# TRL-calibration-thru-reflect-match.net
KiCad netlist of a schematic drawn in EAGLE
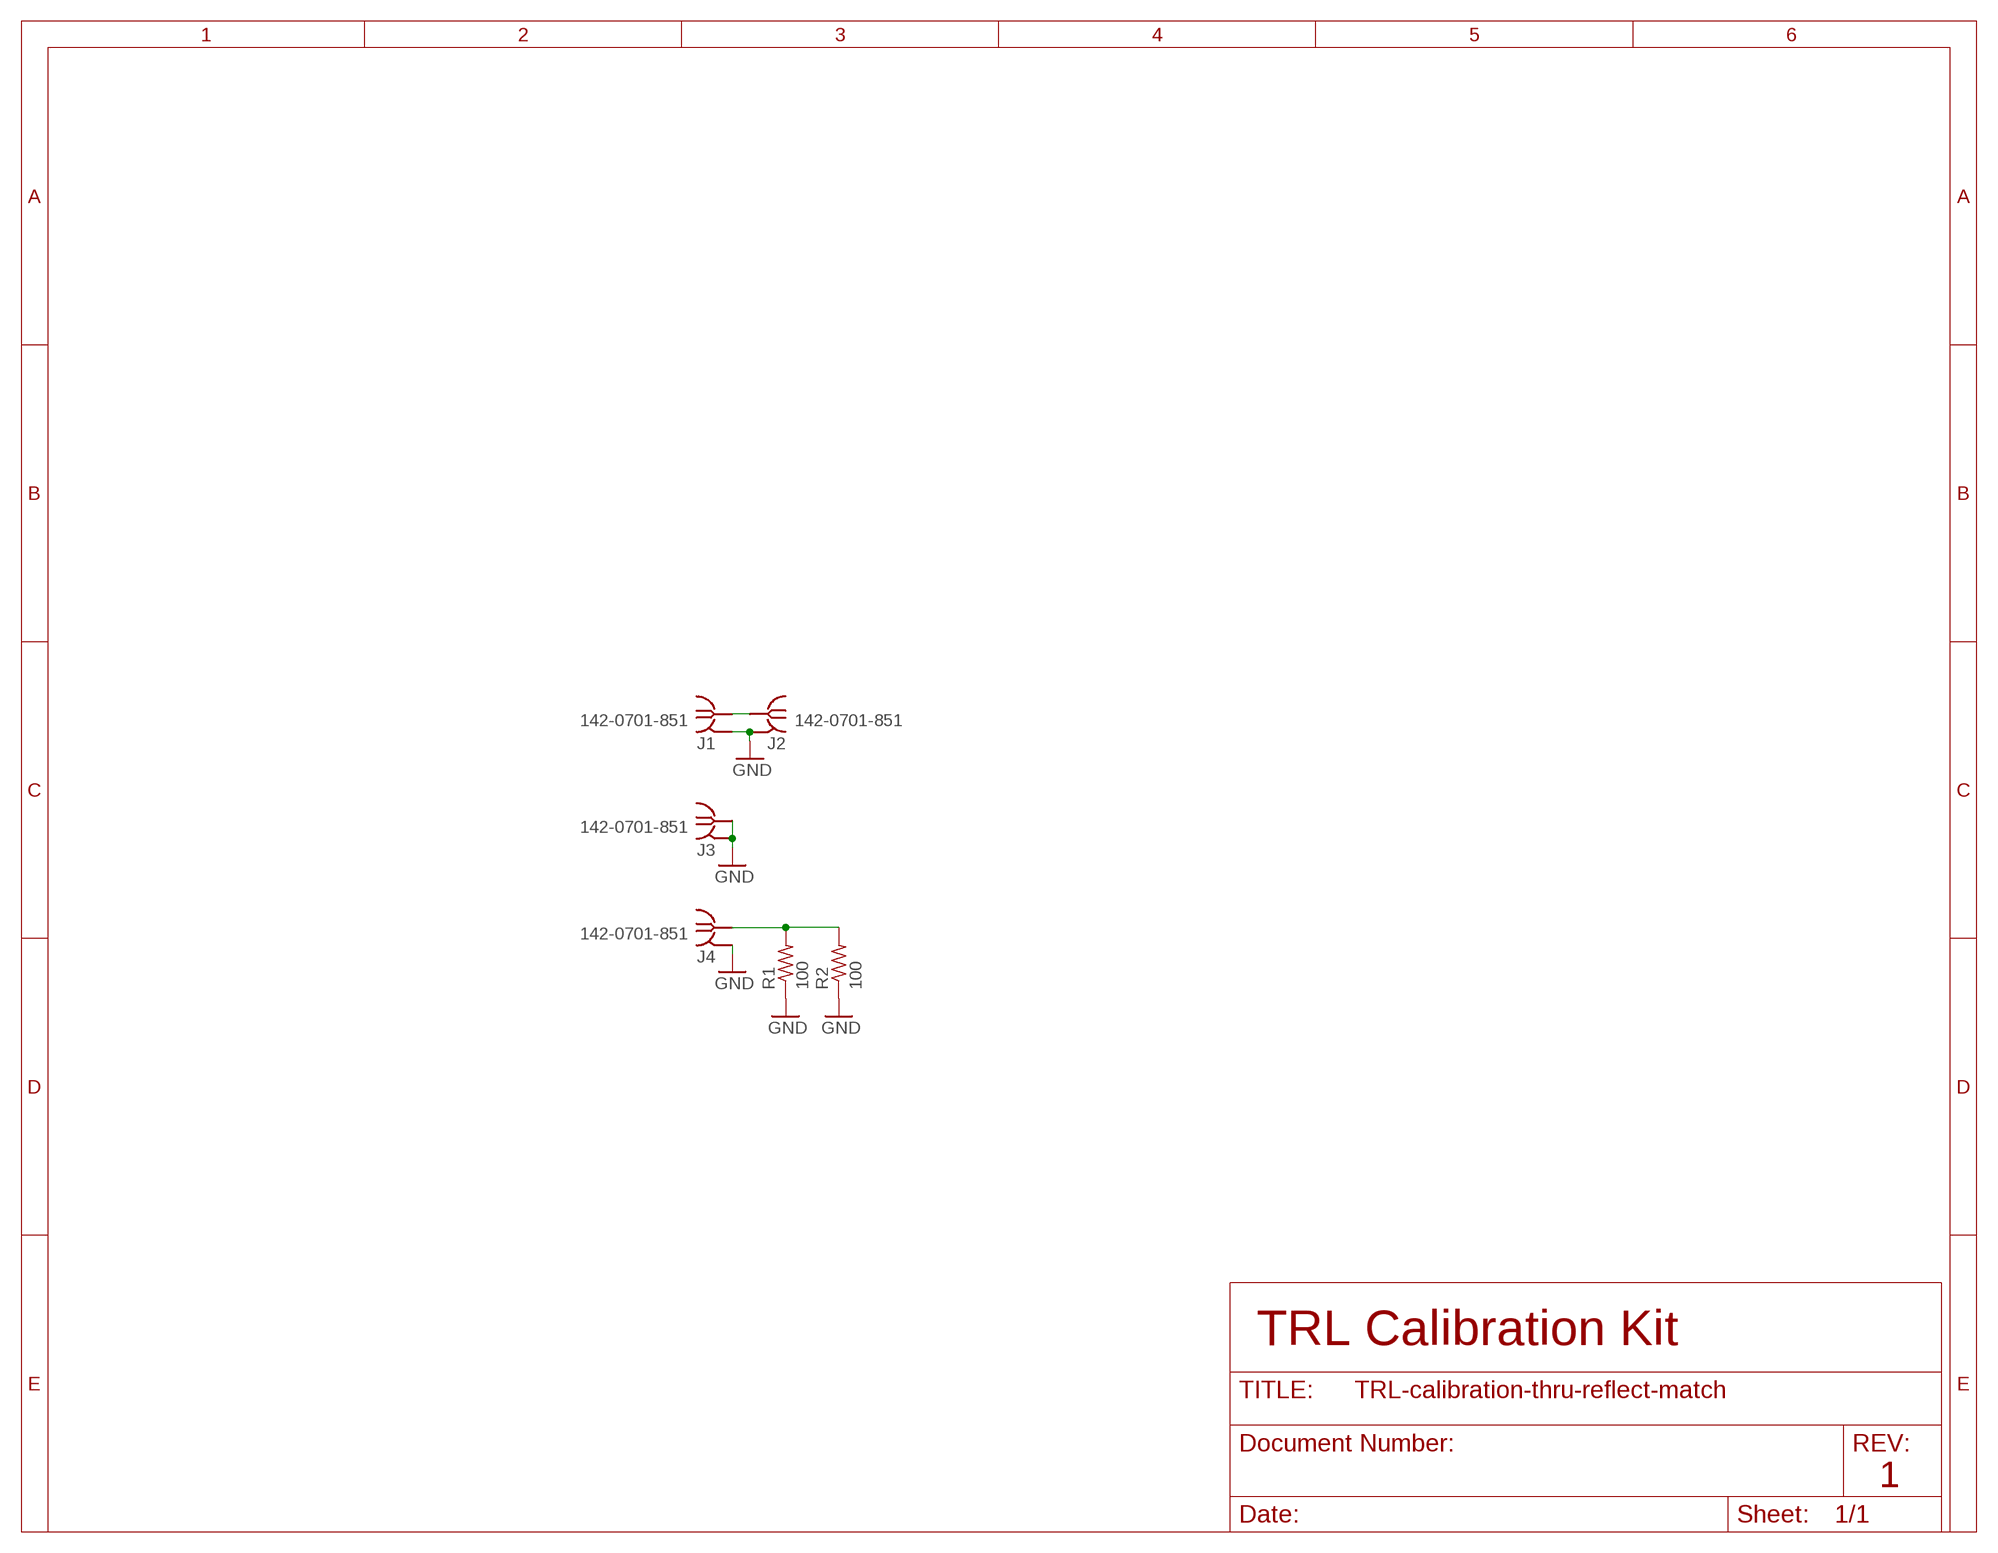
[diagram p0: schematic, sheet 1]

(export (version "E")
  (design (tool "Eeschema 10.0.6"))
  (components
    (comp (ref "J1")
      (value "142-0701-851")
      (footprint "eagle-import:142-0701-851")
      (libsource (lib "eagle-import") (part "142-0701-851"))
    )
    (comp (ref "J2")
      (value "142-0701-851")
      (footprint "eagle-import:142-0701-851")
      (libsource (lib "eagle-import") (part "142-0701-851"))
    )
    (comp (ref "J3")
      (value "142-0701-851")
      (footprint "eagle-import:142-0701-851")
      (libsource (lib "eagle-import") (part "142-0701-851"))
    )
    (comp (ref "J4")
      (value "142-0701-851")
      (footprint "eagle-import:142-0701-851")
      (libsource (lib "eagle-import") (part "142-0701-851"))
    )
    (comp (ref "R1")
      (value "100")
      (footprint "eagle-import:.0402-C-NOSILK")
      (libsource (lib "eagle-import") (part "R-US_0402-C-NOSILK"))
    )
    (comp (ref "R2")
      (value "100")
      (footprint "eagle-import:.0402-C-NOSILK")
      (libsource (lib "eagle-import") (part "R-US_0402-C-NOSILK"))
    )
  )
  (nets
    (net (code "1") (name "GND") (class "Default")
      (node (ref "J1") (pin "GND1") (pinfunction "GND_GND1") (pintype "bidirectional"))
      (node (ref "J1") (pin "GND2") (pinfunction "GND_GND2") (pintype "bidirectional"))
      (node (ref "J1") (pin "GND3") (pinfunction "GND_GND3") (pintype "bidirectional"))
      (node (ref "J1") (pin "GND4") (pinfunction "GND_GND4") (pintype "bidirectional"))
      (node (ref "J2") (pin "GND1") (pinfunction "GND_GND1") (pintype "bidirectional"))
      (node (ref "J2") (pin "GND2") (pinfunction "GND_GND2") (pintype "bidirectional"))
      (node (ref "J2") (pin "GND3") (pinfunction "GND_GND3") (pintype "bidirectional"))
      (node (ref "J2") (pin "GND4") (pinfunction "GND_GND4") (pintype "bidirectional"))
      (node (ref "J3") (pin "GND1") (pinfunction "GND_GND1") (pintype "bidirectional"))
      (node (ref "J3") (pin "GND2") (pinfunction "GND_GND2") (pintype "bidirectional"))
      (node (ref "J3") (pin "GND3") (pinfunction "GND_GND3") (pintype "bidirectional"))
      (node (ref "J3") (pin "GND4") (pinfunction "GND_GND4") (pintype "bidirectional"))
      (node (ref "J3") (pin "RF1") (pinfunction "RF_RF1") (pintype "bidirectional"))
      (node (ref "J4") (pin "GND1") (pinfunction "GND_GND1") (pintype "bidirectional"))
      (node (ref "J4") (pin "GND2") (pinfunction "GND_GND2") (pintype "bidirectional"))
      (node (ref "J4") (pin "GND3") (pinfunction "GND_GND3") (pintype "bidirectional"))
      (node (ref "J4") (pin "GND4") (pinfunction "GND_GND4") (pintype "bidirectional"))
      (node (ref "R1") (pin "1") (pinfunction "1_1") (pintype "passive"))
      (node (ref "R2") (pin "1") (pinfunction "1_1") (pintype "passive"))
    )
    (net (code "2") (name "Net-(J1-RF)") (class "Default")
      (node (ref "J1") (pin "RF1") (pinfunction "RF_RF1") (pintype "bidirectional"))
      (node (ref "J2") (pin "RF1") (pinfunction "RF_RF1") (pintype "bidirectional"))
    )
    (net (code "3") (name "Net-(J4-RF)") (class "Default")
      (node (ref "J4") (pin "RF1") (pinfunction "RF_RF1") (pintype "bidirectional"))
      (node (ref "R1") (pin "2") (pinfunction "2_2") (pintype "passive"))
      (node (ref "R2") (pin "2") (pinfunction "2_2") (pintype "passive"))
    )
  )
)
